# LowduinoPTH_Take3.net
KiCad netlist of a schematic drawn in EAGLE
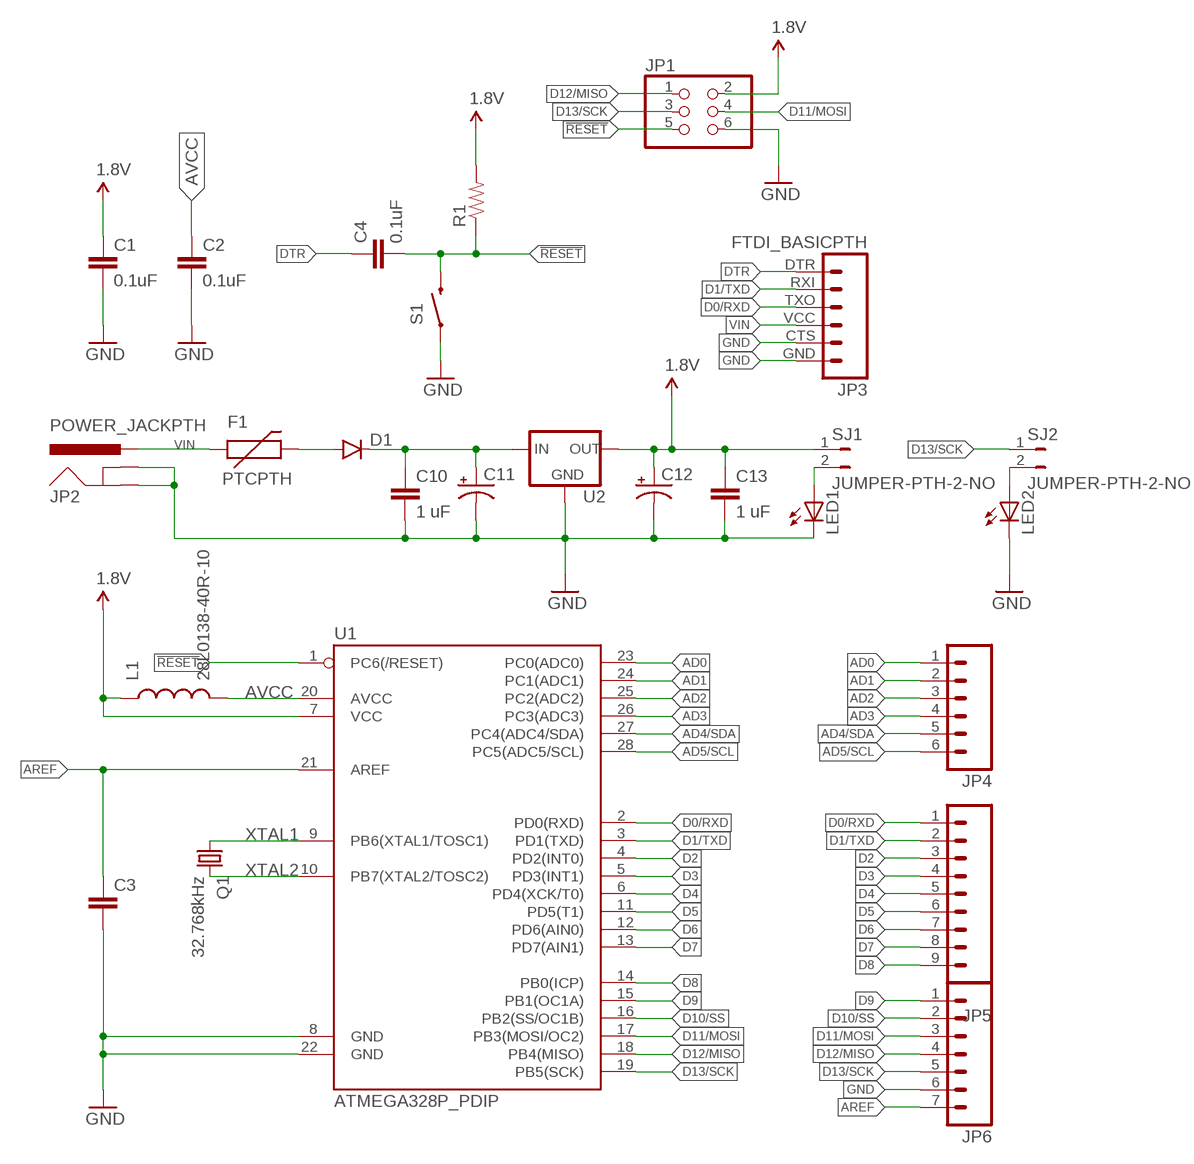
[diagram p0: schematic, sheet 1]

(export (version "E")
  (design (tool "Eeschema 10.0.6"))
  (components
    (comp (ref "C1")
      (value "0.1uF")
      (footprint "eagle-import:CAP-PTH-SMALL2")
      (libsource (lib "eagle-import") (part "CAPPTH2"))
    )
    (comp (ref "C2")
      (value "0.1uF")
      (footprint "eagle-import:CAP-PTH-5MM")
      (libsource (lib "eagle-import") (part "SparkFun-Passives_CAPPTH1"))
    )
    (comp (ref "C3")
      (value "CAPPTH2")
      (footprint "eagle-import:CAP-PTH-SMALL2")
      (libsource (lib "eagle-import") (part "CAPPTH2"))
    )
    (comp (ref "C4")
      (value "0.1uF")
      (footprint "eagle-import:CAP-PTH-SMALL2")
      (libsource (lib "eagle-import") (part "SparkFun-Passives_CAPPTH2"))
    )
    (comp (ref "C10")
      (value "1 uF")
      (footprint "eagle-import:CAP-PTH-SMALL2")
      (libsource (lib "eagle-import") (part "CAPPTH2"))
    )
    (comp (ref "C11")
      (value "CPOL-USE2.5-6")
      (footprint "eagle-import:E2,5-6")
      (libsource (lib "eagle-import") (part "CPOL-USE2.5-6"))
    )
    (comp (ref "C12")
      (value "CPOL-USE2.5-6")
      (footprint "eagle-import:E2,5-6")
      (libsource (lib "eagle-import") (part "CPOL-USE2.5-6"))
    )
    (comp (ref "C13")
      (value "1 uF")
      (footprint "eagle-import:CAP-PTH-SMALL2")
      (libsource (lib "eagle-import") (part "CAPPTH2"))
    )
    (comp (ref "D1")
      (value "DIODEPTH")
      (footprint "eagle-import:DIODE-1N4001")
      (libsource (lib "eagle-import") (part "DIODEPTH"))
    )
    (comp (ref "F1")
      (value "PTCPTH")
      (footprint "eagle-import:PTC")
      (libsource (lib "eagle-import") (part "PTCPTH"))
    )
    (comp (ref "JP1")
      (value "PINHD-2X3")
      (footprint "eagle-import:2X03")
      (libsource (lib "eagle-import") (part "PINHD-2X3"))
    )
    (comp (ref "JP2")
      (value "POWER_JACKPTH")
      (footprint "eagle-import:POWER_JACK_PTH")
      (libsource (lib "eagle-import") (part "POWER_JACKPTH"))
    )
    (comp (ref "JP3")
      (value "FTDI_BASICPTH")
      (footprint "eagle-import:FTDI_BASIC")
      (libsource (lib "eagle-import") (part "FTDI_BASICPTH"))
    )
    (comp (ref "JP4")
      (value "M06SILK_FEMALE_PTH")
      (footprint "eagle-import:1X06")
      (libsource (lib "eagle-import") (part "M06SILK_FEMALE_PTH"))
    )
    (comp (ref "JP5")
      (value "M09")
      (footprint "eagle-import:1X09")
      (libsource (lib "eagle-import") (part "M09"))
    )
    (comp (ref "JP6")
      (value "M07")
      (footprint "eagle-import:1X07")
      (libsource (lib "eagle-import") (part "M07"))
    )
    (comp (ref "L1")
      (value "28L0138-40R-10")
      (footprint "eagle-import:AXIAL-0.6")
      (libsource (lib "eagle-import") (part "INDUCTORAXIAL-0.6"))
    )
    (comp (ref "LED1")
      (value "LED3MM")
      (footprint "eagle-import:LED3MM")
      (libsource (lib "eagle-import") (part "LED3MM"))
    )
    (comp (ref "LED2")
      (value "LED3MM")
      (footprint "eagle-import:LED3MM")
      (libsource (lib "eagle-import") (part "LED3MM"))
    )
    (comp (ref "Q1")
      (value "32.768kHz")
      (footprint "eagle-import:TC26V")
      (libsource (lib "eagle-import") (part "CRYSTALTC26V"))
    )
    (comp (ref "R1")
      (value "RESISTORPTH-1/4W-VERT")
      (footprint "eagle-import:AXIAL-0.1")
      (libsource (lib "eagle-import") (part "RESISTORPTH-1/4W-VERT"))
    )
    (comp (ref "S1")
      (value "SWITCH-MOMENTARY-2PTH")
      (footprint "eagle-import:TACTILE-PTH")
      (libsource (lib "eagle-import") (part "SWITCH-MOMENTARY-2PTH"))
    )
    (comp (ref "SJ1")
      (value "JUMPER-PTH-2-NO")
      (footprint "eagle-import:PTH-JUMPER-2-NO_NO_SILK")
      (libsource (lib "eagle-import") (part "JUMPER-PTH-2-NO"))
    )
    (comp (ref "SJ2")
      (value "JUMPER-PTH-2-NO")
      (footprint "eagle-import:PTH-JUMPER-2-NO_NO_SILK")
      (libsource (lib "eagle-import") (part "JUMPER-PTH-2-NO"))
    )
    (comp (ref "U1")
      (value "ATMEGA328P_PDIP")
      (footprint "eagle-import:DIL28-3")
      (libsource (lib "eagle-import") (part "ATMEGA328P_PDIP"))
    )
    (comp (ref "U2")
      (value "V_REG_78XXTO-92_UNTESTED")
      (footprint "eagle-import:TO-92")
      (libsource (lib "eagle-import") (part "V_REG_78XXTO-92_UNTESTED"))
    )
  )
  (nets
    (net (code "1") (name "/XTAL1") (class "Default")
      (node (ref "Q1") (pin "1") (pinfunction "1_1") (pintype "passive"))
      (node (ref "U1") (pin "9") (pinfunction "PB6(XTAL1/TOSC1)_9") (pintype "bidirectional"))
    )
    (net (code "2") (name "/XTAL2") (class "Default")
      (node (ref "Q1") (pin "2") (pinfunction "2_2") (pintype "passive"))
      (node (ref "U1") (pin "10") (pinfunction "PB7(XTAL2/TOSC2)_10") (pintype "bidirectional"))
    )
    (net (code "3") (name "/~{RESET}") (class "Default")
      (node (ref "C4") (pin "2") (pinfunction "2_2") (pintype "passive"))
      (node (ref "JP1") (pin "5") (pinfunction "5_5") (pintype "passive"))
      (node (ref "R1") (pin "P$1") (pinfunction "1_P$1") (pintype "passive"))
      (node (ref "S1") (pin "3") (pinfunction "2_3") (pintype "passive"))
      (node (ref "U1") (pin "1") (pinfunction "PC6(/RESET)_1") (pintype "bidirectional"))
    )
    (net (code "4") (name "1.8V") (class "Default")
      (node (ref "C1") (pin "1") (pinfunction "1_1") (pintype "passive"))
      (node (ref "C12") (pin "+") (pinfunction "+_+") (pintype "passive"))
      (node (ref "C13") (pin "1") (pinfunction "1_1") (pintype "passive"))
      (node (ref "JP1") (pin "2") (pinfunction "2_2") (pintype "passive"))
      (node (ref "L1") (pin "P$1") (pinfunction "1_P$1") (pintype "passive"))
      (node (ref "R1") (pin "P$2") (pinfunction "2_P$2") (pintype "passive"))
      (node (ref "SJ1") (pin "1") (pinfunction "1_1") (pintype "passive"))
      (node (ref "U1") (pin "7") (pinfunction "VCC_7") (pintype "bidirectional"))
      (node (ref "U2") (pin "3") (pinfunction "OUT_3") (pintype "output"))
    )
    (net (code "5") (name "AD0") (class "Default")
      (node (ref "JP4") (pin "1") (pinfunction "1_1") (pintype "passive"))
      (node (ref "U1") (pin "23") (pinfunction "PC0(ADC0)_23") (pintype "bidirectional"))
    )
    (net (code "6") (name "AD1") (class "Default")
      (node (ref "JP4") (pin "2") (pinfunction "2_2") (pintype "passive"))
      (node (ref "U1") (pin "24") (pinfunction "PC1(ADC1)_24") (pintype "bidirectional"))
    )
    (net (code "7") (name "AD2") (class "Default")
      (node (ref "JP4") (pin "3") (pinfunction "3_3") (pintype "passive"))
      (node (ref "U1") (pin "25") (pinfunction "PC2(ADC2)_25") (pintype "bidirectional"))
    )
    (net (code "8") (name "AD3") (class "Default")
      (node (ref "JP4") (pin "4") (pinfunction "4_4") (pintype "passive"))
      (node (ref "U1") (pin "26") (pinfunction "PC3(ADC3)_26") (pintype "bidirectional"))
    )
    (net (code "9") (name "AD4{slash}SDA") (class "Default")
      (node (ref "JP4") (pin "5") (pinfunction "5_5") (pintype "passive"))
      (node (ref "U1") (pin "27") (pinfunction "PC4(ADC4/SDA)_27") (pintype "bidirectional"))
    )
    (net (code "10") (name "AD5{slash}SCL") (class "Default")
      (node (ref "JP4") (pin "6") (pinfunction "6_6") (pintype "passive"))
      (node (ref "U1") (pin "28") (pinfunction "PC5(ADC5/SCL)_28") (pintype "bidirectional"))
    )
    (net (code "11") (name "AREF") (class "Default")
      (node (ref "C3") (pin "1") (pinfunction "1_1") (pintype "passive"))
      (node (ref "JP6") (pin "7") (pinfunction "7_7") (pintype "passive"))
      (node (ref "U1") (pin "21") (pinfunction "AREF_21") (pintype "bidirectional"))
    )
    (net (code "12") (name "AVCC") (class "Default")
      (node (ref "C2") (pin "1") (pinfunction "1_1") (pintype "passive"))
      (node (ref "L1") (pin "P$2") (pinfunction "2_P$2") (pintype "passive"))
      (node (ref "U1") (pin "20") (pinfunction "AVCC_20") (pintype "bidirectional"))
    )
    (net (code "13") (name "D0{slash}RXD") (class "Default")
      (node (ref "JP3") (pin "TXO") (pinfunction "3_TXO") (pintype "passive"))
      (node (ref "JP5") (pin "1") (pinfunction "1_1") (pintype "passive"))
      (node (ref "U1") (pin "2") (pinfunction "PD0(RXD)_2") (pintype "bidirectional"))
    )
    (net (code "14") (name "D1{slash}TXD") (class "Default")
      (node (ref "JP3") (pin "RXI") (pinfunction "2_RXI") (pintype "passive"))
      (node (ref "JP5") (pin "2") (pinfunction "2_2") (pintype "passive"))
      (node (ref "U1") (pin "3") (pinfunction "PD1(TXD)_3") (pintype "bidirectional"))
    )
    (net (code "15") (name "D2") (class "Default")
      (node (ref "JP5") (pin "3") (pinfunction "3_3") (pintype "passive"))
      (node (ref "U1") (pin "4") (pinfunction "PD2(INT0)_4") (pintype "bidirectional"))
    )
    (net (code "16") (name "D3") (class "Default")
      (node (ref "JP5") (pin "4") (pinfunction "4_4") (pintype "passive"))
      (node (ref "U1") (pin "5") (pinfunction "PD3(INT1)_5") (pintype "bidirectional"))
    )
    (net (code "17") (name "D4") (class "Default")
      (node (ref "JP5") (pin "5") (pinfunction "5_5") (pintype "passive"))
      (node (ref "U1") (pin "6") (pinfunction "PD4(XCK/T0)_6") (pintype "bidirectional"))
    )
    (net (code "18") (name "D5") (class "Default")
      (node (ref "JP5") (pin "6") (pinfunction "6_6") (pintype "passive"))
      (node (ref "U1") (pin "11") (pinfunction "PD5(T1)_11") (pintype "bidirectional"))
    )
    (net (code "19") (name "D6") (class "Default")
      (node (ref "JP5") (pin "7") (pinfunction "7_7") (pintype "passive"))
      (node (ref "U1") (pin "12") (pinfunction "PD6(AIN0)_12") (pintype "bidirectional"))
    )
    (net (code "20") (name "D7") (class "Default")
      (node (ref "JP5") (pin "8") (pinfunction "8_8") (pintype "passive"))
      (node (ref "U1") (pin "13") (pinfunction "PD7(AIN1)_13") (pintype "bidirectional"))
    )
    (net (code "21") (name "D8") (class "Default")
      (node (ref "JP5") (pin "9") (pinfunction "9_9") (pintype "passive"))
      (node (ref "U1") (pin "14") (pinfunction "PB0(ICP)_14") (pintype "bidirectional"))
    )
    (net (code "22") (name "D9") (class "Default")
      (node (ref "JP6") (pin "1") (pinfunction "1_1") (pintype "passive"))
      (node (ref "U1") (pin "15") (pinfunction "PB1(OC1A)_15") (pintype "bidirectional"))
    )
    (net (code "23") (name "D10{slash}SS") (class "Default")
      (node (ref "JP6") (pin "2") (pinfunction "2_2") (pintype "passive"))
      (node (ref "U1") (pin "16") (pinfunction "PB2(SS/OC1B)_16") (pintype "bidirectional"))
    )
    (net (code "24") (name "D11{slash}MOSI") (class "Default")
      (node (ref "JP1") (pin "4") (pinfunction "4_4") (pintype "passive"))
      (node (ref "JP6") (pin "3") (pinfunction "3_3") (pintype "passive"))
      (node (ref "U1") (pin "17") (pinfunction "PB3(MOSI/OC2)_17") (pintype "bidirectional"))
    )
    (net (code "25") (name "D12{slash}MISO") (class "Default")
      (node (ref "JP1") (pin "1") (pinfunction "1_1") (pintype "passive"))
      (node (ref "JP6") (pin "4") (pinfunction "4_4") (pintype "passive"))
      (node (ref "U1") (pin "18") (pinfunction "PB4(MISO)_18") (pintype "bidirectional"))
    )
    (net (code "26") (name "D13{slash}SCK") (class "Default")
      (node (ref "JP1") (pin "3") (pinfunction "3_3") (pintype "passive"))
      (node (ref "JP6") (pin "5") (pinfunction "5_5") (pintype "passive"))
      (node (ref "SJ2") (pin "1") (pinfunction "1_1") (pintype "passive"))
      (node (ref "U1") (pin "19") (pinfunction "PB5(SCK)_19") (pintype "bidirectional"))
    )
    (net (code "27") (name "DTR") (class "Default")
      (node (ref "C4") (pin "1") (pinfunction "1_1") (pintype "passive"))
      (node (ref "JP3") (pin "DTR") (pinfunction "1_DTR") (pintype "passive"))
    )
    (net (code "28") (name "GND") (class "Default")
      (node (ref "C1") (pin "2") (pinfunction "2_2") (pintype "passive"))
      (node (ref "C10") (pin "2") (pinfunction "2_2") (pintype "passive"))
      (node (ref "C11") (pin "-") (pinfunction "-_-") (pintype "passive"))
      (node (ref "C12") (pin "-") (pinfunction "-_-") (pintype "passive"))
      (node (ref "C13") (pin "2") (pinfunction "2_2") (pintype "passive"))
      (node (ref "C2") (pin "2") (pinfunction "2_2") (pintype "passive"))
      (node (ref "C3") (pin "2") (pinfunction "2_2") (pintype "passive"))
      (node (ref "JP1") (pin "6") (pinfunction "6_6") (pintype "passive"))
      (node (ref "JP2") (pin "GND") (pinfunction "GND_GND") (pintype "bidirectional"))
      (node (ref "JP2") (pin "GNDBREAK") (pinfunction "GNDBREAK_GNDBREAK") (pintype "bidirectional"))
      (node (ref "JP3") (pin "CTS") (pinfunction "5_CTS") (pintype "passive"))
      (node (ref "JP3") (pin "GND") (pinfunction "6_GND") (pintype "passive"))
      (node (ref "JP6") (pin "6") (pinfunction "6_6") (pintype "passive"))
      (node (ref "LED1") (pin "K") (pinfunction "C_K") (pintype "passive"))
      (node (ref "LED2") (pin "K") (pinfunction "C_K") (pintype "passive"))
      (node (ref "S1") (pin "1") (pinfunction "1_1") (pintype "passive"))
      (node (ref "U1") (pin "22") (pinfunction "GND_22") (pintype "bidirectional"))
      (node (ref "U1") (pin "8") (pinfunction "GND_8") (pintype "bidirectional"))
      (node (ref "U2") (pin "1") (pinfunction "GND_1") (pintype "input"))
    )
    (net (code "29") (name "Net-(F1-2)") (class "Default")
      (node (ref "D1") (pin "A") (pinfunction "A_A") (pintype "passive"))
      (node (ref "F1") (pin "P$2") (pinfunction "2_P$2") (pintype "bidirectional"))
    )
    (net (code "30") (name "Net-(LED1-PadA)") (class "Default")
      (node (ref "LED1") (pin "A") (pinfunction "A_A") (pintype "passive"))
      (node (ref "SJ1") (pin "2") (pinfunction "2_2") (pintype "passive"))
    )
    (net (code "31") (name "Net-(LED2-PadA)") (class "Default")
      (node (ref "LED2") (pin "A") (pinfunction "A_A") (pintype "passive"))
      (node (ref "SJ2") (pin "2") (pinfunction "2_2") (pintype "passive"))
    )
    (net (code "32") (name "Net-(U2-IN)") (class "Default")
      (node (ref "C10") (pin "1") (pinfunction "1_1") (pintype "passive"))
      (node (ref "C11") (pin "+") (pinfunction "+_+") (pintype "passive"))
      (node (ref "D1") (pin "C") (pinfunction "C_C") (pintype "passive"))
      (node (ref "U2") (pin "2") (pinfunction "IN_2") (pintype "input"))
    )
    (net (code "33") (name "VIN") (class "Default")
      (node (ref "F1") (pin "P$1") (pinfunction "1_P$1") (pintype "bidirectional"))
      (node (ref "JP2") (pin "PWR") (pinfunction "PWR_PWR") (pintype "bidirectional"))
      (node (ref "JP3") (pin "VCC") (pinfunction "4_VCC") (pintype "passive"))
    )
  )
)
